# SolderStation.net
KiCad netlist of a schematic drawn in Altium Designer
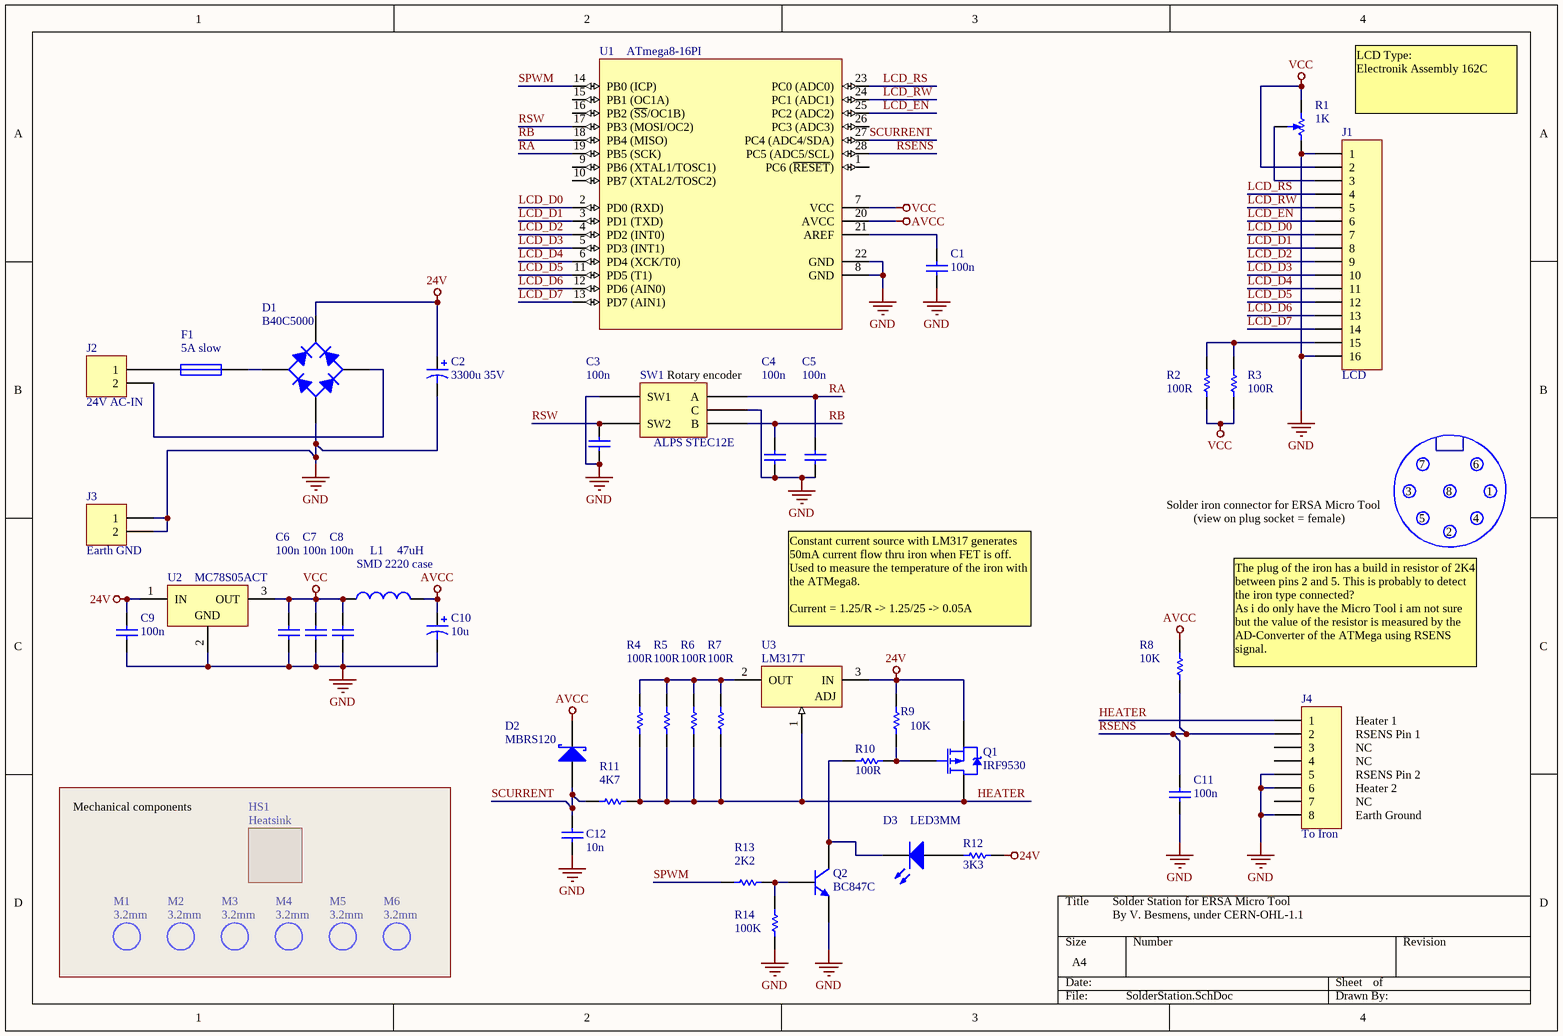
[diagram p0: SolderStation.SchDoc]

(export (version "E")
  (design (tool "Eeschema 10.0.6"))
  (components
    (comp (ref "C1")
      (value "100n")
      (footprint "C0805")
      (description "Capacitor (Semiconductor SIM Model)")
      (fields (field (name "Comment") "Cap Semi") (field (name "PUBLISHER") "Altium Limited"))
      (libsource (lib "Miscellaneous Devices") (part "Cap Semi"))
    )
    (comp (ref "C2")
      (value "3300u 35V")
      (footprint "RBM-3.5/8.0")
      (description "Polarized Capacitor (Surface Mount)")
      (fields (field (name "PUBLISHER") "Altium Limited"))
      (libsource (lib "Miscellaneous Devices") (part "Cap Pol3"))
    )
    (comp (ref "C3")
      (value "100n")
      (footprint "C0805")
      (description "Capacitor (Semiconductor SIM Model)")
      (fields (field (name "Comment") "Cap Semi") (field (name "PUBLISHER") "Altium Limited"))
      (libsource (lib "Miscellaneous Devices") (part "Cap Semi"))
    )
    (comp (ref "C4")
      (value "100n")
      (footprint "C0805")
      (description "Capacitor (Semiconductor SIM Model)")
      (fields (field (name "Comment") "Cap Semi") (field (name "PUBLISHER") "Altium Limited"))
      (libsource (lib "Miscellaneous Devices") (part "Cap Semi"))
    )
    (comp (ref "C5")
      (value "100n")
      (footprint "C0805")
      (description "Capacitor (Semiconductor SIM Model)")
      (fields (field (name "Comment") "Cap Semi") (field (name "PUBLISHER") "Altium Limited"))
      (libsource (lib "Miscellaneous Devices") (part "Cap Semi"))
    )
    (comp (ref "C6")
      (value "100n")
      (footprint "C0805")
      (description "Capacitor (Semiconductor SIM Model)")
      (fields (field (name "Comment") "Cap Semi") (field (name "PUBLISHER") "Altium Limited"))
      (libsource (lib "Miscellaneous Devices") (part "Cap Semi"))
    )
    (comp (ref "C7")
      (value "100n")
      (footprint "C0805")
      (description "Capacitor (Semiconductor SIM Model)")
      (fields (field (name "Comment") "Cap Semi") (field (name "PUBLISHER") "Altium Limited"))
      (libsource (lib "Miscellaneous Devices") (part "Cap Semi"))
    )
    (comp (ref "C8")
      (value "100n")
      (footprint "C0805")
      (description "Capacitor (Semiconductor SIM Model)")
      (fields (field (name "Comment") "Cap Semi") (field (name "PUBLISHER") "Altium Limited"))
      (libsource (lib "Miscellaneous Devices") (part "Cap Semi"))
    )
    (comp (ref "C9")
      (value "100n")
      (footprint "C0805")
      (description "Capacitor (Semiconductor SIM Model)")
      (fields (field (name "Comment") "Cap Semi") (field (name "PUBLISHER") "Altium Limited"))
      (libsource (lib "Miscellaneous Devices") (part "Cap Semi"))
    )
    (comp (ref "C10")
      (value "10u")
      (footprint "RBM-1.5/4.0")
      (description "Polarized Capacitor (Surface Mount)")
      (fields (field (name "PUBLISHER") "Altium Limited"))
      (libsource (lib "Miscellaneous Devices") (part "Cap Pol3"))
    )
    (comp (ref "C11")
      (value "100n")
      (footprint "C0805")
      (description "Capacitor (Semiconductor SIM Model)")
      (fields (field (name "Comment") "Cap Semi") (field (name "PUBLISHER") "Altium Limited"))
      (libsource (lib "Miscellaneous Devices") (part "Cap Semi"))
    )
    (comp (ref "C12")
      (value "10n")
      (footprint "C0805")
      (description "Capacitor (Semiconductor SIM Model)")
      (fields (field (name "Comment") "Cap Semi") (field (name "PUBLISHER") "Altium Limited"))
      (libsource (lib "Miscellaneous Devices") (part "Cap Semi"))
    )
    (comp (ref "D1")
      (value "B40C5000")
      (footprint "VB:BXXC5000")
      (description "Full Wave Diode Bridge")
      (fields (field (name "PUBLISHER") "Altium Limited"))
      (libsource (lib "Miscellaneous Devices") (part "Bridge1"))
    )
    (comp (ref "D2")
      (value "MBRS120")
      (footprint "D_SMB")
      (description "Schottky Diode")
      (fields (field (name "PUBLISHER") "Altium Limited"))
      (libsource (lib "Miscellaneous Devices") (part "D Schottky"))
    )
    (comp (ref "D3")
      (value "LED3MM")
      (footprint "VB:LED1206R")
      (description "Typical INFRARED GaAs LED")
      (fields (field (name "PUBLISHER") "Altium Limited"))
      (libsource (lib "Miscellaneous Devices") (part "LED0"))
    )
    (comp (ref "F1")
      (value "5A slow")
      (footprint "PIN-W2/E2.8")
      (description "Fuse")
      (fields (field (name "PUBLISHER") "Altium Limited"))
      (libsource (lib "Miscellaneous Devices") (part "Fuse 1"))
    )
    (comp (ref "HS1")
      (value "Heatsink")
      (footprint "Heatsink_VPR116 - L46")
      (description "Heatsink Symbol")
      (libsource (lib "*") (part "Heatsink"))
    )
    (comp (ref "J1")
      (value "LCD")
      (footprint "HDR1X16")
      (description "Header, 16-Pin")
      (fields (field (name "PUBLISHER") "Altium Limited"))
      (libsource (lib "Miscellaneous Connectors") (part "Header 16"))
    )
    (comp (ref "J2")
      (value "24V AC-IN")
      (footprint "MKDS3_2RMI")
      (description "Header, 2-Pin")
      (fields (field (name "PUBLISHER") "Altium Limited"))
      (libsource (lib "Miscellaneous Connectors") (part "Header 2"))
    )
    (comp (ref "J3")
      (value "Earth GND")
      (footprint "MKDS3_2RMI")
      (description "Header, 2-Pin")
      (fields (field (name "PUBLISHER") "Altium Limited"))
      (libsource (lib "Miscellaneous Connectors") (part "Header 2"))
    )
    (comp (ref "J4")
      (value "To Iron")
      (footprint "PSS8G")
      (description "Header, 8-Pin")
      (fields (field (name "PUBLISHER") "Altium Limited"))
      (libsource (lib "Miscellaneous Connectors") (part "Header 8"))
    )
    (comp (ref "L1")
      (value "47uH")
      (footprint "INDC1608L")
      (description "Inductor")
      (fields (field (name "Comment") "47u") (field (name "PUBLISHER") "Altium Limited"))
      (libsource (lib "Miscellaneous Devices") (part "Inductor"))
    )
    (comp (ref "M1")
      (value "3.2mm")
      (footprint "DRILL3_2MM")
      (description "Mounting Hole")
      (libsource (lib "*") (part "MountingHole"))
    )
    (comp (ref "M2")
      (value "3.2mm")
      (footprint "DRILL3_2MM")
      (description "Mounting Hole")
      (libsource (lib "*") (part "MountingHole"))
    )
    (comp (ref "M3")
      (value "3.2mm")
      (footprint "DRILL3_2MM")
      (description "Mounting Hole")
      (libsource (lib "*") (part "MountingHole"))
    )
    (comp (ref "M4")
      (value "3.2mm")
      (footprint "DRILL3_2MM")
      (description "Mounting Hole")
      (libsource (lib "*") (part "MountingHole"))
    )
    (comp (ref "M5")
      (value "3.2mm")
      (footprint "DRILL3_2MM")
      (description "Mounting Hole")
      (libsource (lib "*") (part "MountingHole"))
    )
    (comp (ref "M6")
      (value "3.2mm")
      (footprint "DRILL3_2MM")
      (description "Mounting Hole")
      (libsource (lib "*") (part "MountingHole"))
    )
    (comp (ref "Q1")
      (value "IRF9530")
      (footprint "VB:TO-220-3VI")
      (description "HEXFET P-Channel Power MOSFET")
      (fields (field (name "PUBLISHER") "Altium Limited"))
      (libsource (lib "IR Discrete MOSFET - Power") (part "IRF9530"))
    )
    (comp (ref "Q2")
      (value "BC847C")
      (footprint "SOT23")
      (description "NPN General-purpose Transistor")
      (fields (field (name "PUBLISHER") "Altium Limited"))
      (libsource (lib "Philips Discrete BJT - Low Power") (part "BC847C"))
    )
    (comp (ref "R1")
      (value "1K")
      (footprint "VR-7")
      (description "Square Trimming Potentiometer")
      (fields (field (name "PUBLISHER") "Altium Limited"))
      (libsource (lib "Miscellaneous Devices") (part "RPot SM"))
    )
    (comp (ref "R2")
      (value "100R")
      (footprint "R0805")
      (description "Resistor")
      (fields (field (name "Comment") "Res1") (field (name "PUBLISHER") "Altium Limited"))
      (libsource (lib "Miscellaneous Devices") (part "Res1"))
    )
    (comp (ref "R3")
      (value "100R")
      (footprint "R0805")
      (description "Resistor")
      (fields (field (name "Comment") "Res1") (field (name "PUBLISHER") "Altium Limited"))
      (libsource (lib "Miscellaneous Devices") (part "Res1"))
    )
    (comp (ref "R4")
      (value "100R")
      (footprint "R0805")
      (description "Resistor")
      (fields (field (name "Comment") "Res1") (field (name "PUBLISHER") "Altium Limited"))
      (libsource (lib "Miscellaneous Devices") (part "Res1"))
    )
    (comp (ref "R5")
      (value "100R")
      (footprint "R0805")
      (description "Resistor")
      (fields (field (name "Comment") "Res1") (field (name "PUBLISHER") "Altium Limited"))
      (libsource (lib "Miscellaneous Devices") (part "Res1"))
    )
    (comp (ref "R6")
      (value "100R")
      (footprint "R0805")
      (description "Resistor")
      (fields (field (name "Comment") "Res1") (field (name "PUBLISHER") "Altium Limited"))
      (libsource (lib "Miscellaneous Devices") (part "Res1"))
    )
    (comp (ref "R7")
      (value "100R")
      (footprint "R0805")
      (description "Resistor")
      (fields (field (name "Comment") "Res1") (field (name "PUBLISHER") "Altium Limited"))
      (libsource (lib "Miscellaneous Devices") (part "Res1"))
    )
    (comp (ref "R8")
      (value "10K")
      (footprint "R0805")
      (description "Resistor")
      (fields (field (name "Comment") "Res1") (field (name "PUBLISHER") "Altium Limited"))
      (libsource (lib "Miscellaneous Devices") (part "Res1"))
    )
    (comp (ref "R9")
      (value "10K")
      (footprint "R0805")
      (description "Resistor")
      (fields (field (name "Comment") "Res1") (field (name "PUBLISHER") "Altium Limited"))
      (libsource (lib "Miscellaneous Devices") (part "Res1"))
    )
    (comp (ref "R10")
      (value "100R")
      (footprint "R0805")
      (description "Resistor")
      (fields (field (name "Comment") "Res1") (field (name "PUBLISHER") "Altium Limited"))
      (libsource (lib "Miscellaneous Devices") (part "Res1"))
    )
    (comp (ref "R11")
      (value "4K7")
      (footprint "R0805")
      (description "Resistor")
      (fields (field (name "Comment") "Res1") (field (name "PUBLISHER") "Altium Limited"))
      (libsource (lib "Miscellaneous Devices") (part "Res1"))
    )
    (comp (ref "R12")
      (value "3K3")
      (footprint "R0805")
      (description "Resistor")
      (fields (field (name "Comment") "Res1") (field (name "PUBLISHER") "Altium Limited"))
      (libsource (lib "Miscellaneous Devices") (part "Res1"))
    )
    (comp (ref "R13")
      (value "2K2")
      (footprint "R0805")
      (description "Resistor")
      (fields (field (name "Comment") "Res1") (field (name "PUBLISHER") "Altium Limited"))
      (libsource (lib "Miscellaneous Devices") (part "Res1"))
    )
    (comp (ref "R14")
      (value "100K")
      (footprint "R0805")
      (description "Resistor")
      (fields (field (name "Comment") "Res1") (field (name "PUBLISHER") "Altium Limited"))
      (libsource (lib "Miscellaneous Devices") (part "Res1"))
    )
    (comp (ref "SW1")
      (value "ALPS STEC12E")
      (footprint "VB:ALPS_STEC12E08")
      (libsource (lib "VB") (part "RotaryEncoder"))
    )
    (comp (ref "U1")
      (value "ATmega8-16PI")
      (footprint "DIP-28S")
      (description "8-Bit AVR Microcontroller with 8K Bytes of In-System Programmable Flash Memory")
      (fields (field (name "PUBLISHER") "Altium Limited"))
      (libsource (lib "Atmel Microcontroller 8-Bit AVR") (part "ATmega8-16PI"))
    )
    (comp (ref "U2")
      (value "MC78S05ACT")
      (footprint "TO-220-3VI")
      (description "3-Terminal Positive Fixed Voltage Regulator")
      (fields (field (name "PUBLISHER") "Altium Limited"))
      (libsource (lib "Motorola Power Mgt Voltage Regulator") (part "MC7805ACT"))
    )
    (comp (ref "U3")
      (value "LM317T")
      (footprint "VB:TO220V")
      (description "3-Terminal Adjustable Positive Voltage Regulator")
      (fields (field (name "PUBLISHER") "Altium Limited"))
      (libsource (lib "Motorola Power Mgt Voltage Regulator") (part "LM317T"))
    )
  )
  (nets
    (net (code "1") (name "/HEATER") (class "Default")
      (node (ref "J4") (pin "1") (pinfunction "1_1") (pintype "passive"))
      (node (ref "Q1") (pin "2") (pinfunction "D_2") (pintype "passive"))
      (node (ref "R11") (pin "2") (pinfunction "2_2") (pintype "passive"))
      (node (ref "R4") (pin "2") (pinfunction "2_2") (pintype "passive"))
      (node (ref "R5") (pin "2") (pinfunction "2_2") (pintype "passive"))
      (node (ref "R6") (pin "2") (pinfunction "2_2") (pintype "passive"))
      (node (ref "R7") (pin "2") (pinfunction "2_2") (pintype "passive"))
      (node (ref "U3") (pin "1") (pinfunction "ADJ_1") (pintype "input"))
    )
    (net (code "2") (name "/LCD_D0") (class "Default")
      (node (ref "J1") (pin "7") (pinfunction "7_7") (pintype "passive"))
      (node (ref "U1") (pin "2") (pinfunction "PD0_(RXD)_2") (pintype "bidirectional"))
    )
    (net (code "3") (name "/LCD_D1") (class "Default")
      (node (ref "J1") (pin "8") (pinfunction "8_8") (pintype "passive"))
      (node (ref "U1") (pin "3") (pinfunction "PD1_(TXD)_3") (pintype "bidirectional"))
    )
    (net (code "4") (name "/LCD_D2") (class "Default")
      (node (ref "J1") (pin "9") (pinfunction "9_9") (pintype "passive"))
      (node (ref "U1") (pin "4") (pinfunction "PD2_(INT0)_4") (pintype "bidirectional"))
    )
    (net (code "5") (name "/LCD_D3") (class "Default")
      (node (ref "J1") (pin "10") (pinfunction "10_10") (pintype "passive"))
      (node (ref "U1") (pin "5") (pinfunction "PD3_(INT1)_5") (pintype "bidirectional"))
    )
    (net (code "6") (name "/LCD_D4") (class "Default")
      (node (ref "J1") (pin "11") (pinfunction "11_11") (pintype "passive"))
      (node (ref "U1") (pin "6") (pinfunction "PD4_(XCK/T0)_6") (pintype "bidirectional"))
    )
    (net (code "7") (name "/LCD_D5") (class "Default")
      (node (ref "J1") (pin "12") (pinfunction "12_12") (pintype "passive"))
      (node (ref "U1") (pin "11") (pinfunction "PD5_(T1)_11") (pintype "bidirectional"))
    )
    (net (code "8") (name "/LCD_D6") (class "Default")
      (node (ref "J1") (pin "13") (pinfunction "13_13") (pintype "passive"))
      (node (ref "U1") (pin "12") (pinfunction "PD6_(AIN0)_12") (pintype "bidirectional"))
    )
    (net (code "9") (name "/LCD_D7") (class "Default")
      (node (ref "J1") (pin "14") (pinfunction "14_14") (pintype "passive"))
      (node (ref "U1") (pin "13") (pinfunction "PD7_(AIN1)_13") (pintype "bidirectional"))
    )
    (net (code "10") (name "/LCD_EN") (class "Default")
      (node (ref "J1") (pin "6") (pinfunction "6_6") (pintype "passive"))
      (node (ref "U1") (pin "25") (pinfunction "PC2_(ADC2)_25") (pintype "bidirectional"))
    )
    (net (code "11") (name "/LCD_RS") (class "Default")
      (node (ref "J1") (pin "4") (pinfunction "4_4") (pintype "passive"))
      (node (ref "U1") (pin "23") (pinfunction "PC0_(ADC0)_23") (pintype "bidirectional"))
    )
    (net (code "12") (name "/LCD_RW") (class "Default")
      (node (ref "J1") (pin "5") (pinfunction "5_5") (pintype "passive"))
      (node (ref "U1") (pin "24") (pinfunction "PC1_(ADC1)_24") (pintype "bidirectional"))
    )
    (net (code "13") (name "/RA") (class "Default")
      (node (ref "C5") (pin "2") (pinfunction "2_2") (pintype "passive"))
      (node (ref "SW1") (pin "A") (pinfunction "A_A") (pintype "passive"))
      (node (ref "U1") (pin "19") (pinfunction "PB5_(SCK)_19") (pintype "bidirectional"))
    )
    (net (code "14") (name "/RB") (class "Default")
      (node (ref "C4") (pin "2") (pinfunction "2_2") (pintype "passive"))
      (node (ref "SW1") (pin "B") (pinfunction "B_B") (pintype "passive"))
      (node (ref "U1") (pin "18") (pinfunction "PB4_(MISO)_18") (pintype "bidirectional"))
    )
    (net (code "15") (name "/RSENS") (class "Default")
      (node (ref "C11") (pin "2") (pinfunction "2_2") (pintype "passive"))
      (node (ref "J4") (pin "2") (pinfunction "2_2") (pintype "passive"))
      (node (ref "R8") (pin "1") (pinfunction "1_1") (pintype "passive"))
      (node (ref "U1") (pin "28") (pinfunction "PC5_(ADC5/SCL)_28") (pintype "bidirectional"))
    )
    (net (code "16") (name "/RSW") (class "Default")
      (node (ref "C3") (pin "2") (pinfunction "2_2") (pintype "passive"))
      (node (ref "SW1") (pin "SW2") (pinfunction "SW2_SW2") (pintype "passive"))
      (node (ref "U1") (pin "17") (pinfunction "PB3_(MOSI/OC2)_17") (pintype "bidirectional"))
    )
    (net (code "17") (name "/SCURRENT") (class "Default")
      (node (ref "C12") (pin "2") (pinfunction "2_2") (pintype "passive"))
      (node (ref "D2") (pin "1") (pinfunction "A_1") (pintype "passive"))
      (node (ref "R11") (pin "1") (pinfunction "1_1") (pintype "passive"))
      (node (ref "U1") (pin "27") (pinfunction "PC4_(ADC4/SDA)_27") (pintype "bidirectional"))
    )
    (net (code "18") (name "/SPWM") (class "Default")
      (node (ref "R13") (pin "2") (pinfunction "2_2") (pintype "passive"))
      (node (ref "U1") (pin "14") (pinfunction "PB0_(ICP)_14") (pintype "bidirectional"))
    )
    (net (code "19") (name "24V") (class "Default")
      (node (ref "C2") (pin "1") (pinfunction "1_1") (pintype "passive"))
      (node (ref "C9") (pin "2") (pinfunction "2_2") (pintype "passive"))
      (node (ref "D1") (pin "1") (pinfunction "K_1") (pintype "passive"))
      (node (ref "Q1") (pin "3") (pinfunction "S_3") (pintype "passive"))
      (node (ref "R12") (pin "1") (pinfunction "1_1") (pintype "passive"))
      (node (ref "R9") (pin "2") (pinfunction "2_2") (pintype "passive"))
      (node (ref "U2") (pin "1") (pinfunction "IN_1") (pintype "power_in"))
      (node (ref "U3") (pin "3") (pinfunction "IN_3") (pintype "power_in"))
    )
    (net (code "20") (name "AVCC") (class "Default")
      (node (ref "C10") (pin "1") (pinfunction "1_1") (pintype "passive"))
      (node (ref "D2") (pin "2") (pinfunction "K_2") (pintype "passive"))
      (node (ref "L1") (pin "2") (pinfunction "2_2") (pintype "passive"))
      (node (ref "R8") (pin "2") (pinfunction "2_2") (pintype "passive"))
      (node (ref "U1") (pin "20") (pinfunction "AVCC_20") (pintype "power_in"))
    )
    (net (code "21") (name "GND") (class "Default")
      (node (ref "C1") (pin "1") (pinfunction "1_1") (pintype "passive"))
      (node (ref "C10") (pin "2") (pinfunction "2_2") (pintype "passive"))
      (node (ref "C11") (pin "1") (pinfunction "1_1") (pintype "passive"))
      (node (ref "C12") (pin "1") (pinfunction "1_1") (pintype "passive"))
      (node (ref "C2") (pin "2") (pinfunction "2_2") (pintype "passive"))
      (node (ref "C3") (pin "1") (pinfunction "1_1") (pintype "passive"))
      (node (ref "C4") (pin "1") (pinfunction "1_1") (pintype "passive"))
      (node (ref "C5") (pin "1") (pinfunction "1_1") (pintype "passive"))
      (node (ref "C6") (pin "1") (pinfunction "1_1") (pintype "passive"))
      (node (ref "C7") (pin "1") (pinfunction "1_1") (pintype "passive"))
      (node (ref "C8") (pin "1") (pinfunction "1_1") (pintype "passive"))
      (node (ref "C9") (pin "1") (pinfunction "1_1") (pintype "passive"))
      (node (ref "D1") (pin "3") (pinfunction "A_3") (pintype "passive"))
      (node (ref "J1") (pin "1") (pinfunction "1_1") (pintype "passive"))
      (node (ref "J1") (pin "16") (pinfunction "16_16") (pintype "passive"))
      (node (ref "J3") (pin "1") (pinfunction "1_1") (pintype "passive"))
      (node (ref "J3") (pin "2") (pinfunction "2_2") (pintype "passive"))
      (node (ref "J4") (pin "5") (pinfunction "5_5") (pintype "passive"))
      (node (ref "J4") (pin "6") (pinfunction "6_6") (pintype "passive"))
      (node (ref "J4") (pin "8") (pinfunction "8_8") (pintype "passive"))
      (node (ref "Q2") (pin "2") (pinfunction "E_2") (pintype "passive"))
      (node (ref "R1") (pin "3") (pinfunction "+_3") (pintype "passive"))
      (node (ref "R14") (pin "2") (pinfunction "2_2") (pintype "passive"))
      (node (ref "SW1") (pin "C") (pinfunction "C_C") (pintype "passive"))
      (node (ref "SW1") (pin "SW1") (pinfunction "SW1_SW1") (pintype "passive"))
      (node (ref "U1") (pin "22") (pinfunction "GND_22") (pintype "power_in"))
      (node (ref "U1") (pin "8") (pinfunction "GND_8") (pintype "power_in"))
      (node (ref "U2") (pin "2") (pinfunction "GND_2") (pintype "power_in"))
    )
    (net (code "22") (name "Net-(D1-C-Pad2)") (class "Default")
      (node (ref "D1") (pin "2") (pinfunction "C_2") (pintype "passive"))
      (node (ref "J2") (pin "2") (pinfunction "2_2") (pintype "passive"))
    )
    (net (code "23") (name "Net-(D1-C-Pad4)") (class "Default")
      (node (ref "D1") (pin "4") (pinfunction "C_4") (pintype "passive"))
      (node (ref "F1") (pin "2") (pinfunction "2_2") (pintype "passive"))
    )
    (net (code "24") (name "Net-(D3-A)") (class "Default")
      (node (ref "D3") (pin "1") (pinfunction "A_1") (pintype "passive"))
      (node (ref "R12") (pin "2") (pinfunction "2_2") (pintype "passive"))
    )
    (net (code "25") (name "Net-(D3-K)") (class "Default")
      (node (ref "D3") (pin "2") (pinfunction "K_2") (pintype "passive"))
      (node (ref "Q2") (pin "3") (pinfunction "C_3") (pintype "passive"))
      (node (ref "R10") (pin "2") (pinfunction "2_2") (pintype "passive"))
    )
    (net (code "26") (name "Net-(F1-Pad1)") (class "Default")
      (node (ref "F1") (pin "1") (pinfunction "1_1") (pintype "passive"))
      (node (ref "J2") (pin "1") (pinfunction "1_1") (pintype "passive"))
    )
    (net (code "27") (name "Net-(J1-Pad15)") (class "Default")
      (node (ref "J1") (pin "15") (pinfunction "15_15") (pintype "passive"))
      (node (ref "R2") (pin "1") (pinfunction "1_1") (pintype "passive"))
      (node (ref "R3") (pin "1") (pinfunction "1_1") (pintype "passive"))
    )
    (net (code "28") (name "Net-(Q1-G)") (class "Default")
      (node (ref "Q1") (pin "1") (pinfunction "G_1") (pintype "passive"))
      (node (ref "R10") (pin "1") (pinfunction "1_1") (pintype "passive"))
      (node (ref "R9") (pin "1") (pinfunction "1_1") (pintype "passive"))
    )
    (net (code "29") (name "Net-(Q2-B)") (class "Default")
      (node (ref "Q2") (pin "1") (pinfunction "B_1") (pintype "passive"))
      (node (ref "R13") (pin "1") (pinfunction "1_1") (pintype "passive"))
      (node (ref "R14") (pin "1") (pinfunction "1_1") (pintype "passive"))
    )
    (net (code "30") (name "Net-(R1-W)") (class "Default")
      (node (ref "J1") (pin "3") (pinfunction "3_3") (pintype "passive"))
      (node (ref "R1") (pin "2") (pinfunction "W_2") (pintype "passive"))
    )
    (net (code "31") (name "Net-(U1-AREF)") (class "Default")
      (node (ref "C1") (pin "2") (pinfunction "2_2") (pintype "passive"))
      (node (ref "U1") (pin "21") (pinfunction "AREF_21") (pintype "passive"))
    )
    (net (code "32") (name "Net-(U3-OUT)") (class "Default")
      (node (ref "R4") (pin "1") (pinfunction "1_1") (pintype "passive"))
      (node (ref "R5") (pin "1") (pinfunction "1_1") (pintype "passive"))
      (node (ref "R6") (pin "1") (pinfunction "1_1") (pintype "passive"))
      (node (ref "R7") (pin "1") (pinfunction "1_1") (pintype "passive"))
      (node (ref "U3") (pin "2") (pinfunction "OUT_2") (pintype "power_in"))
    )
    (net (code "33") (name "VCC") (class "Default")
      (node (ref "C6") (pin "2") (pinfunction "2_2") (pintype "passive"))
      (node (ref "C7") (pin "2") (pinfunction "2_2") (pintype "passive"))
      (node (ref "C8") (pin "2") (pinfunction "2_2") (pintype "passive"))
      (node (ref "J1") (pin "2") (pinfunction "2_2") (pintype "passive"))
      (node (ref "L1") (pin "1") (pinfunction "1_1") (pintype "passive"))
      (node (ref "R1") (pin "1") (pinfunction "-_1") (pintype "passive"))
      (node (ref "R2") (pin "2") (pinfunction "2_2") (pintype "passive"))
      (node (ref "R3") (pin "2") (pinfunction "2_2") (pintype "passive"))
      (node (ref "U1") (pin "7") (pinfunction "VCC_7") (pintype "power_in"))
      (node (ref "U2") (pin "3") (pinfunction "OUT_3") (pintype "power_in"))
    )
    (net (code "34") (name "unconnected-(J4-Pad3)") (class "Default")
      (node (ref "J4") (pin "3") (pinfunction "3_3") (pintype "passive"))
    )
    (net (code "35") (name "unconnected-(J4-Pad4)") (class "Default")
      (node (ref "J4") (pin "4") (pinfunction "4_4") (pintype "passive"))
    )
    (net (code "36") (name "unconnected-(J4-Pad7)") (class "Default")
      (node (ref "J4") (pin "7") (pinfunction "7_7") (pintype "passive"))
    )
    (net (code "37") (name "unconnected-(U1-PB1_(OC1A)-Pad15)") (class "Default")
      (node (ref "U1") (pin "15") (pinfunction "PB1_(OC1A)_15") (pintype "bidirectional"))
    )
    (net (code "38") (name "unconnected-(U1-PB2_(~{SS}{slash}OC1B)-Pad16)") (class "Default")
      (node (ref "U1") (pin "16") (pinfunction "PB2_(~{SS}/OC1B)_16") (pintype "bidirectional"))
    )
    (net (code "39") (name "unconnected-(U1-PB6_(XTAL1{slash}TOSC1)-Pad9)") (class "Default")
      (node (ref "U1") (pin "9") (pinfunction "PB6_(XTAL1/TOSC1)_9") (pintype "bidirectional"))
    )
    (net (code "40") (name "unconnected-(U1-PB7_(XTAL2{slash}TOSC2)-Pad10)") (class "Default")
      (node (ref "U1") (pin "10") (pinfunction "PB7_(XTAL2/TOSC2)_10") (pintype "bidirectional"))
    )
    (net (code "41") (name "unconnected-(U1-PC3_(ADC3)-Pad26)") (class "Default")
      (node (ref "U1") (pin "26") (pinfunction "PC3_(ADC3)_26") (pintype "bidirectional"))
    )
    (net (code "42") (name "unconnected-(U1-PC6_(~{RESET})-Pad1)") (class "Default")
      (node (ref "U1") (pin "1") (pinfunction "PC6_(~{RESET})_1") (pintype "bidirectional"))
    )
  )
)
